# Lasermodul.net
KiCad netlist of a schematic drawn in EAGLE
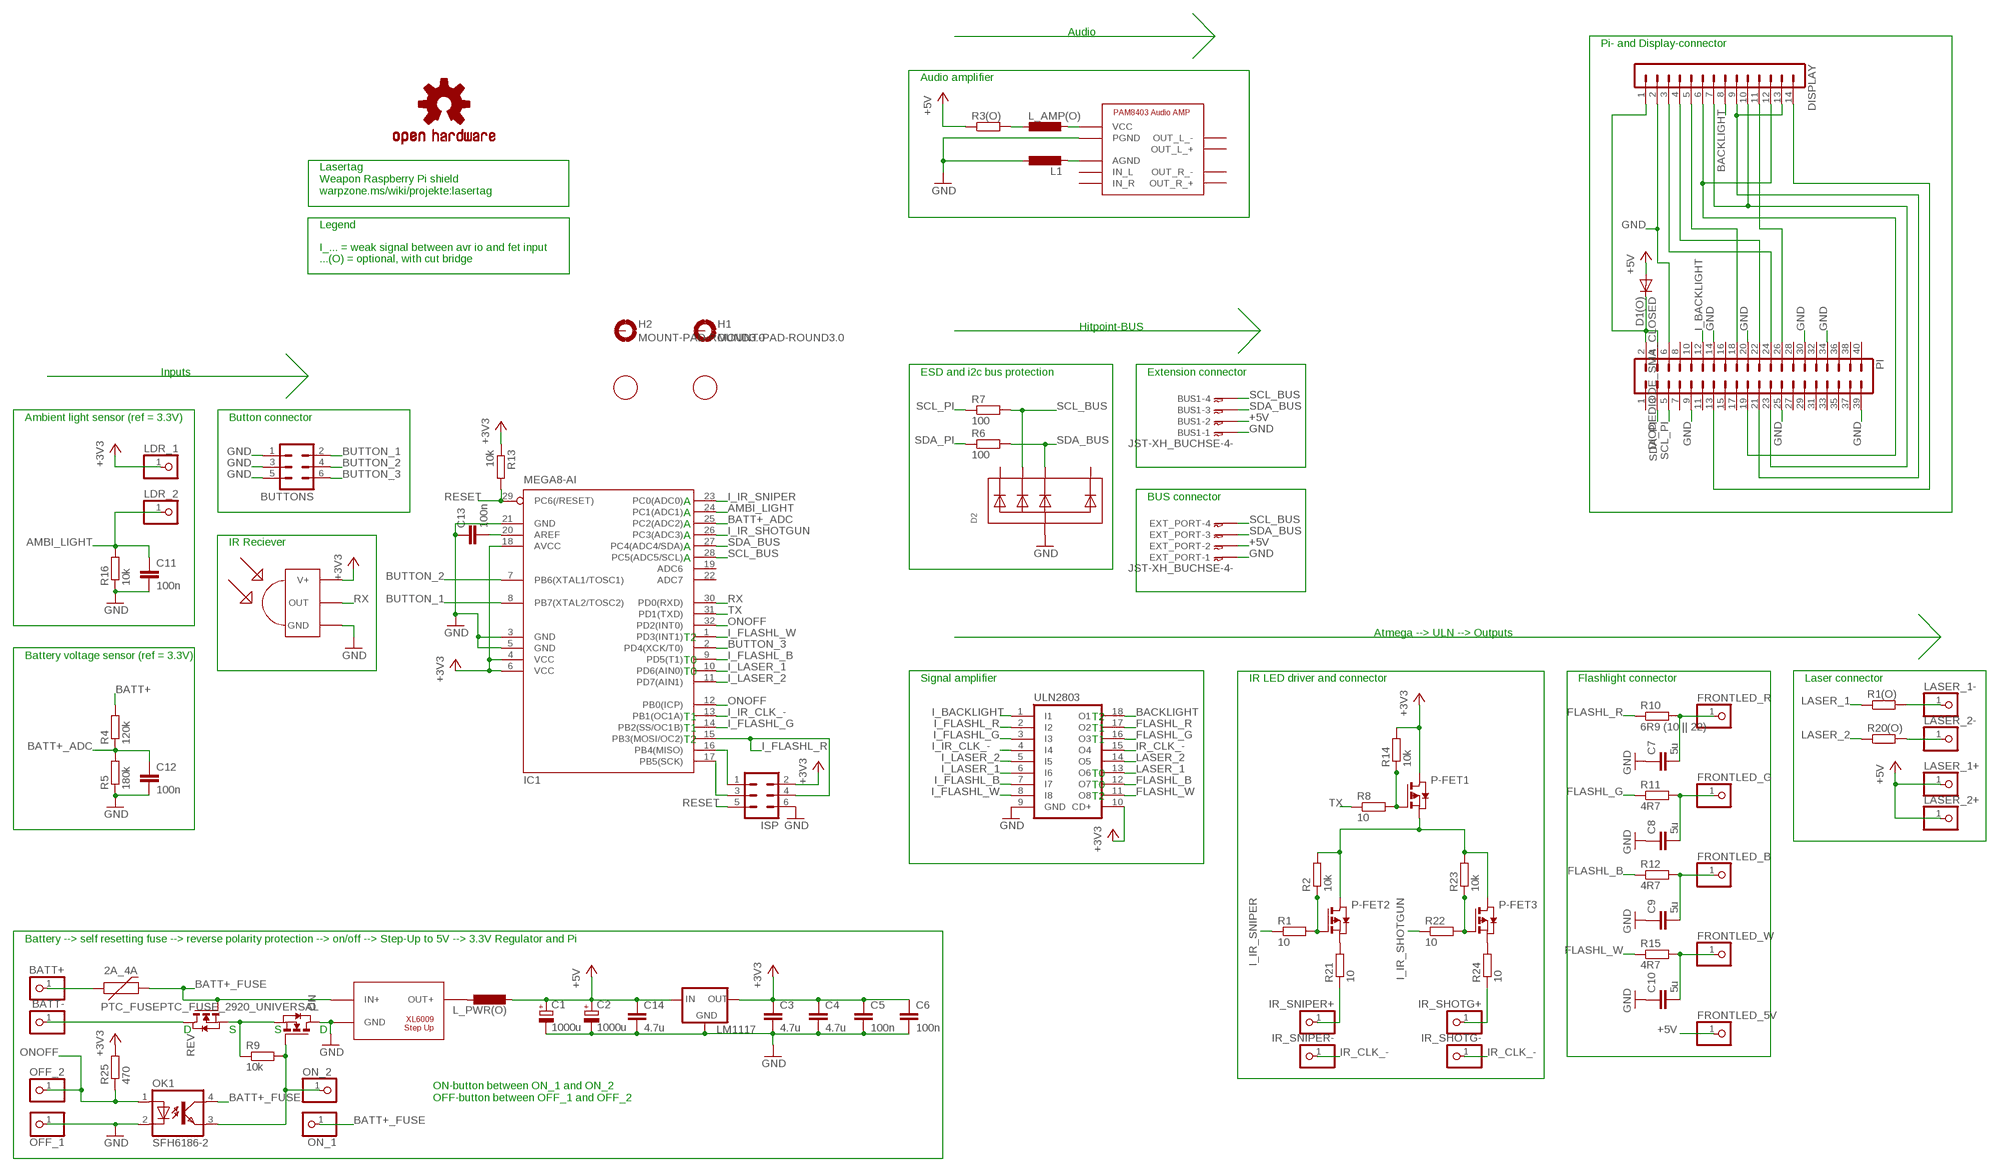
[diagram p0: schematic, sheet 1]

(export (version "E")
  (design (tool "Eeschema 10.0.6"))
  (components
    (comp (ref "2A_4A")
      (value "PTC_FUSEPTC_FUSE_2920_UNIVERSAL")
      (footprint "eagle-import:PTC_FUSE_2920_UNIVERSAL")
      (libsource (lib "eagle-import") (part "PTC_FUSEPTC_FUSE_2920_UNIVERSAL"))
    )
    (comp (ref "BATT+")
      (value "PIN-HEADER-1PIN-HEADER-1_BIG")
      (footprint "eagle-import:PIN-HEADER-1_BIG")
      (libsource (lib "eagle-import") (part "PIN-HEADER-1PIN-HEADER-1_BIG"))
    )
    (comp (ref "BATT-")
      (value "PIN-HEADER-1PIN-HEADER-1_BIG")
      (footprint "eagle-import:PIN-HEADER-1_BIG")
      (libsource (lib "eagle-import") (part "PIN-HEADER-1PIN-HEADER-1_BIG"))
    )
    (comp (ref "BUS1")
      (value "JST-XH_BUCHSE-4-")
      (footprint "eagle-import:JST-XH_BUCHSE-4")
      (libsource (lib "eagle-import") (part "JST-XH_BUCHSE-4-"))
    )
    (comp (ref "BUTTONS")
      (value "PIN-HEADER-3X2")
      (footprint "eagle-import:PIN-HEADER-3X2")
      (libsource (lib "eagle-import") (part "PIN-HEADER-3X2"))
    )
    (comp (ref "C1")
      (value "1000u")
      (footprint "eagle-import:C_UNIVERSAL_PAD")
      (libsource (lib "eagle-import") (part "C_EU_POL"))
    )
    (comp (ref "C2")
      (value "1000u")
      (footprint "eagle-import:C_UNIVERSAL_PAD")
      (libsource (lib "eagle-import") (part "C_EU_POL"))
    )
    (comp (ref "C3")
      (value "4.7u")
      (footprint "eagle-import:0805")
      (libsource (lib "eagle-import") (part "C_EU0805"))
    )
    (comp (ref "C4")
      (value "4.7u")
      (footprint "eagle-import:0805")
      (libsource (lib "eagle-import") (part "C_EU0805"))
    )
    (comp (ref "C5")
      (value "100n")
      (footprint "eagle-import:0603")
      (libsource (lib "eagle-import") (part "C_EU0603"))
    )
    (comp (ref "C6")
      (value "100n")
      (footprint "eagle-import:0603")
      (libsource (lib "eagle-import") (part "C_EU0603"))
    )
    (comp (ref "C7")
      (value "5u")
      (footprint "eagle-import:0805")
      (libsource (lib "eagle-import") (part "C_EU0805"))
    )
    (comp (ref "C8")
      (value "5u")
      (footprint "eagle-import:0805")
      (libsource (lib "eagle-import") (part "C_EU0805"))
    )
    (comp (ref "C9")
      (value "5u")
      (footprint "eagle-import:0805")
      (libsource (lib "eagle-import") (part "C_EU0805"))
    )
    (comp (ref "C10")
      (value "5u")
      (footprint "eagle-import:0805")
      (libsource (lib "eagle-import") (part "C_EU0805"))
    )
    (comp (ref "C11")
      (value "100n")
      (footprint "eagle-import:0603")
      (libsource (lib "eagle-import") (part "C_EU0603"))
    )
    (comp (ref "C12")
      (value "100n")
      (footprint "eagle-import:0603")
      (libsource (lib "eagle-import") (part "C_EU0603"))
    )
    (comp (ref "C13")
      (value "100n")
      (footprint "eagle-import:0603")
      (libsource (lib "eagle-import") (part "C_EU0603"))
    )
    (comp (ref "C14")
      (value "4.7u")
      (footprint "eagle-import:0805")
      (libsource (lib "eagle-import") (part "C_EU0805"))
    )
    (comp (ref "D1(O)")
      (value "DIODEDIODE_SMA_CLOSED")
      (footprint "eagle-import:DIODE_SMA_CLOSED")
      (libsource (lib "eagle-import") (part "DIODEDIODE_SMA_CLOSED"))
    )
    (comp (ref "D2")
      (value "ESD-SCHUTZ")
      (footprint "eagle-import:SOT363")
      (libsource (lib "eagle-import") (part "ESD-SCHUTZ"))
    )
    (comp (ref "DISPLAY")
      (value "PIN-HEADER-DISPLAY")
      (footprint "eagle-import:PIN-HEADER-DISPLAY")
      (libsource (lib "eagle-import") (part "PIN-HEADER-DISPLAY"))
    )
    (comp (ref "EXT_PORT")
      (value "JST-XH_BUCHSE-4-")
      (footprint "eagle-import:JST-XH_BUCHSE-4")
      (libsource (lib "eagle-import") (part "JST-XH_BUCHSE-4-"))
    )
    (comp (ref "FRONTLED_5V")
      (value "PIN-HEADER-1PIN-HEADER-1")
      (footprint "eagle-import:PIN-HEADER-1")
      (libsource (lib "eagle-import") (part "PIN-HEADER-1PIN-HEADER-1"))
    )
    (comp (ref "FRONTLED_B")
      (value "PIN-HEADER-1PIN-HEADER-1")
      (footprint "eagle-import:PIN-HEADER-1")
      (libsource (lib "eagle-import") (part "PIN-HEADER-1PIN-HEADER-1"))
    )
    (comp (ref "FRONTLED_G")
      (value "PIN-HEADER-1PIN-HEADER-1")
      (footprint "eagle-import:PIN-HEADER-1")
      (libsource (lib "eagle-import") (part "PIN-HEADER-1PIN-HEADER-1"))
    )
    (comp (ref "FRONTLED_R")
      (value "PIN-HEADER-1PIN-HEADER-1")
      (footprint "eagle-import:PIN-HEADER-1")
      (libsource (lib "eagle-import") (part "PIN-HEADER-1PIN-HEADER-1"))
    )
    (comp (ref "FRONTLED_W")
      (value "PIN-HEADER-1PIN-HEADER-1")
      (footprint "eagle-import:PIN-HEADER-1")
      (libsource (lib "eagle-import") (part "PIN-HEADER-1PIN-HEADER-1"))
    )
    (comp (ref "H1")
      (value "MOUNT-PAD-ROUND3.0")
      (footprint "eagle-import:3,0-PAD")
      (libsource (lib "eagle-import") (part "MOUNT-PAD-ROUND3.0"))
    )
    (comp (ref "H2")
      (value "MOUNT-PAD-ROUND3.0")
      (footprint "eagle-import:3,0-PAD")
      (libsource (lib "eagle-import") (part "MOUNT-PAD-ROUND3.0"))
    )
    (comp (ref "IC1")
      (value "MEGA8-AI")
      (footprint "eagle-import:TQFP32-08")
      (fields (field (name "MPN") "ATMEGA8-16AU"))
      (libsource (lib "eagle-import") (part "MEGA8-AI"))
    )
    (comp (ref "IR_SHOTG+")
      (value "PIN-HEADER-1PIN-HEADER-1")
      (footprint "eagle-import:PIN-HEADER-1")
      (libsource (lib "eagle-import") (part "PIN-HEADER-1PIN-HEADER-1"))
    )
    (comp (ref "IR_SHOTG-")
      (value "PIN-HEADER-1PIN-HEADER-1")
      (footprint "eagle-import:PIN-HEADER-1")
      (libsource (lib "eagle-import") (part "PIN-HEADER-1PIN-HEADER-1"))
    )
    (comp (ref "IR_SNIPER+")
      (value "PIN-HEADER-1PIN-HEADER-1")
      (footprint "eagle-import:PIN-HEADER-1")
      (libsource (lib "eagle-import") (part "PIN-HEADER-1PIN-HEADER-1"))
    )
    (comp (ref "IR_SNIPER-")
      (value "PIN-HEADER-1PIN-HEADER-1")
      (footprint "eagle-import:PIN-HEADER-1")
      (libsource (lib "eagle-import") (part "PIN-HEADER-1PIN-HEADER-1"))
    )
    (comp (ref "ISP")
      (value "PIN-HEADER-3X2")
      (footprint "eagle-import:PIN-HEADER-3X2")
      (libsource (lib "eagle-import") (part "PIN-HEADER-3X2"))
    )
    (comp (ref "L1")
      (value "L-EUL2825P")
      (footprint "eagle-import:L2825P")
      (libsource (lib "eagle-import") (part "L-EUL2825P"))
    )
    (comp (ref "LASER_1+")
      (value "PIN-HEADER-1PIN-HEADER-1")
      (footprint "eagle-import:PIN-HEADER-1")
      (libsource (lib "eagle-import") (part "PIN-HEADER-1PIN-HEADER-1"))
    )
    (comp (ref "LASER_1-")
      (value "PIN-HEADER-1PIN-HEADER-1")
      (footprint "eagle-import:PIN-HEADER-1")
      (libsource (lib "eagle-import") (part "PIN-HEADER-1PIN-HEADER-1"))
    )
    (comp (ref "LASER_2+")
      (value "PIN-HEADER-1PIN-HEADER-1")
      (footprint "eagle-import:PIN-HEADER-1")
      (libsource (lib "eagle-import") (part "PIN-HEADER-1PIN-HEADER-1"))
    )
    (comp (ref "LASER_2-")
      (value "PIN-HEADER-1PIN-HEADER-1")
      (footprint "eagle-import:PIN-HEADER-1")
      (libsource (lib "eagle-import") (part "PIN-HEADER-1PIN-HEADER-1"))
    )
    (comp (ref "LDR_1")
      (value "PIN-HEADER-1PIN-HEADER-1")
      (footprint "eagle-import:PIN-HEADER-1")
      (libsource (lib "eagle-import") (part "PIN-HEADER-1PIN-HEADER-1"))
    )
    (comp (ref "LDR_2")
      (value "PIN-HEADER-1PIN-HEADER-1")
      (footprint "eagle-import:PIN-HEADER-1")
      (libsource (lib "eagle-import") (part "PIN-HEADER-1PIN-HEADER-1"))
    )
    (comp (ref "LM1117")
      (value "LM1117_3V3_REGULATOR")
      (footprint "eagle-import:SOT223")
      (libsource (lib "eagle-import") (part "LM1117_3V3_REGULATOR"))
    )
    (comp (ref "LOGO1")
      (value "OSHW-LOGOM")
      (footprint "eagle-import:OSHW-LOGO-M")
      (libsource (lib "eagle-import") (part "OSHW-LOGOM"))
    )
    (comp (ref "L_AMP(O)")
      (value "L")
      (footprint "eagle-import:L_5MM_CLOSED")
      (libsource (lib "eagle-import") (part "L"))
    )
    (comp (ref "L_PWR(O)")
      (value "L")
      (footprint "eagle-import:L_5MM_CLOSED")
      (libsource (lib "eagle-import") (part "L"))
    )
    (comp (ref "OFF_1")
      (value "PIN-HEADER-1PIN-HEADER-1")
      (footprint "eagle-import:PIN-HEADER-1")
      (libsource (lib "eagle-import") (part "PIN-HEADER-1PIN-HEADER-1"))
    )
    (comp (ref "OFF_2")
      (value "PIN-HEADER-1PIN-HEADER-1")
      (footprint "eagle-import:PIN-HEADER-1")
      (libsource (lib "eagle-import") (part "PIN-HEADER-1PIN-HEADER-1"))
    )
    (comp (ref "OK1")
      (value "SFH6186-2")
      (footprint "eagle-import:SMD4-7")
      (fields (field (name "MF") "VISHAY/TELEFUNKEN"))
      (libsource (lib "eagle-import") (part "SFH618?6-2"))
    )
    (comp (ref "ON")
      (value "N-MOSFET")
      (footprint "eagle-import:TO252")
      (libsource (lib "eagle-import") (part "N-MOSFET"))
    )
    (comp (ref "ON_1")
      (value "PIN-HEADER-1PIN-HEADER-1")
      (footprint "eagle-import:PIN-HEADER-1")
      (libsource (lib "eagle-import") (part "PIN-HEADER-1PIN-HEADER-1"))
    )
    (comp (ref "ON_2")
      (value "PIN-HEADER-1PIN-HEADER-1")
      (footprint "eagle-import:PIN-HEADER-1")
      (libsource (lib "eagle-import") (part "PIN-HEADER-1PIN-HEADER-1"))
    )
    (comp (ref "P-FET1")
      (value "PMOSSOT23")
      (footprint "eagle-import:SOT-23")
      (libsource (lib "eagle-import") (part "PMOSSOT23"))
    )
    (comp (ref "P-FET2")
      (value "PMOSSOT23")
      (footprint "eagle-import:SOT-23")
      (libsource (lib "eagle-import") (part "PMOSSOT23"))
    )
    (comp (ref "P-FET3")
      (value "PMOSSOT23")
      (footprint "eagle-import:SOT-23")
      (libsource (lib "eagle-import") (part "PMOSSOT23"))
    )
    (comp (ref "PI")
      (value "PIN-HEADER-20X2")
      (footprint "eagle-import:PIN-HEADER-20X2")
      (libsource (lib "eagle-import") (part "PIN-HEADER-20X2"))
    )
    (comp (ref "R1")
      (value "10")
      (footprint "eagle-import:0603")
      (libsource (lib "eagle-import") (part "R_EU0603"))
    )
    (comp (ref "R1(O)")
      (value "R_EU0603_CLOSED")
      (footprint "eagle-import:0603_CLOSED")
      (libsource (lib "eagle-import") (part "R_EU0603_CLOSED"))
    )
    (comp (ref "R2")
      (value "10k")
      (footprint "eagle-import:0603")
      (libsource (lib "eagle-import") (part "R_EU0603"))
    )
    (comp (ref "R3(O)")
      (value "R_EU0805_CLOSED")
      (footprint "eagle-import:0805_CLOSED")
      (libsource (lib "eagle-import") (part "R_EU0805_CLOSED"))
    )
    (comp (ref "R4")
      (value "120k")
      (footprint "eagle-import:0603")
      (libsource (lib "eagle-import") (part "R_EU0603"))
    )
    (comp (ref "R5")
      (value "180k")
      (footprint "eagle-import:0603")
      (libsource (lib "eagle-import") (part "R_EU0603"))
    )
    (comp (ref "R6")
      (value "100")
      (footprint "eagle-import:0603")
      (libsource (lib "eagle-import") (part "R_EU0603"))
    )
    (comp (ref "R7")
      (value "100")
      (footprint "eagle-import:0603")
      (libsource (lib "eagle-import") (part "R_EU0603"))
    )
    (comp (ref "R8")
      (value "10")
      (footprint "eagle-import:0603")
      (libsource (lib "eagle-import") (part "R_EU0603"))
    )
    (comp (ref "R9")
      (value "10k")
      (footprint "eagle-import:0603")
      (libsource (lib "eagle-import") (part "R_EU0603"))
    )
    (comp (ref "R10")
      (value "6R9 (10 || 22)")
      (footprint "eagle-import:0603")
      (libsource (lib "eagle-import") (part "R_EU0603"))
    )
    (comp (ref "R11")
      (value "4R7")
      (footprint "eagle-import:0603")
      (libsource (lib "eagle-import") (part "R_EU0603"))
    )
    (comp (ref "R12")
      (value "4R7")
      (footprint "eagle-import:0603")
      (libsource (lib "eagle-import") (part "R_EU0603"))
    )
    (comp (ref "R13")
      (value "10k")
      (footprint "eagle-import:0603")
      (libsource (lib "eagle-import") (part "R_EU0603"))
    )
    (comp (ref "R14")
      (value "10k")
      (footprint "eagle-import:0603")
      (libsource (lib "eagle-import") (part "R_EU0603"))
    )
    (comp (ref "R15")
      (value "4R7")
      (footprint "eagle-import:0603")
      (libsource (lib "eagle-import") (part "R_EU0603"))
    )
    (comp (ref "R16")
      (value "10k")
      (footprint "eagle-import:0603")
      (libsource (lib "eagle-import") (part "R_EU0603"))
    )
    (comp (ref "R20(O)")
      (value "R_EU0603_CLOSED")
      (footprint "eagle-import:0603_CLOSED")
      (libsource (lib "eagle-import") (part "R_EU0603_CLOSED"))
    )
    (comp (ref "R21")
      (value "10")
      (footprint "eagle-import:0603")
      (libsource (lib "eagle-import") (part "R_EU0603"))
    )
    (comp (ref "R22")
      (value "10")
      (footprint "eagle-import:0603")
      (libsource (lib "eagle-import") (part "R_EU0603"))
    )
    (comp (ref "R23")
      (value "10k")
      (footprint "eagle-import:0603")
      (libsource (lib "eagle-import") (part "R_EU0603"))
    )
    (comp (ref "R24")
      (value "10")
      (footprint "eagle-import:0603")
      (libsource (lib "eagle-import") (part "R_EU0603"))
    )
    (comp (ref "R25")
      (value "470")
      (footprint "eagle-import:0603")
      (libsource (lib "eagle-import") (part "R_EU0603"))
    )
    (comp (ref "REV")
      (value "N-MOSFET")
      (footprint "eagle-import:TO252")
      (libsource (lib "eagle-import") (part "N-MOSFET"))
    )
    (comp (ref "U$1")
      (value "TSOP1838")
      (footprint "eagle-import:TSOP18XX")
      (libsource (lib "eagle-import") (part "TSOP1838"))
    )
    (comp (ref "U$3")
      (value "XL6009-STEPUP-BOARD")
      (footprint "eagle-import:XL6009-STEPUP-BOARD")
      (libsource (lib "eagle-import") (part "XL6009-STEPUP-BOARD"))
    )
    (comp (ref "U$4")
      (value "PAM8403-AMP-BOARD")
      (footprint "eagle-import:PAM8403-AMP-BOARD")
      (libsource (lib "eagle-import") (part "PAM8403-AMP-BOARD"))
    )
    (comp (ref "U$5")
      (value "FIDUCIAL")
      (footprint "eagle-import:FIDUCIAL_1MM")
      (libsource (lib "eagle-import") (part "FIDUCIAL"))
    )
    (comp (ref "U$6")
      (value "FIDUCIAL")
      (footprint "eagle-import:FIDUCIAL_1MM")
      (libsource (lib "eagle-import") (part "FIDUCIAL"))
    )
    (comp (ref "ULN2803")
      (value "ULN2803ASO18")
      (footprint "eagle-import:SO18W")
      (libsource (lib "eagle-import") (part "ULN2803ASO18"))
    )
  )
  (nets
    (net (code "1") (name "+3V3") (class "Default")
      (node (ref "C3") (pin "1") (pinfunction "1_1") (pintype "passive"))
      (node (ref "C4") (pin "1") (pinfunction "1_1") (pintype "passive"))
      (node (ref "C5") (pin "1") (pinfunction "1_1") (pintype "passive"))
      (node (ref "C6") (pin "1") (pinfunction "1_1") (pintype "passive"))
      (node (ref "IC1") (pin "18") (pinfunction "AVCC_18") (pintype "power_in"))
      (node (ref "IC1") (pin "4") (pinfunction "VCC_4") (pintype "power_in"))
      (node (ref "IC1") (pin "6") (pinfunction "VCC_6") (pintype "power_in"))
      (node (ref "ISP") (pin "2") (pinfunction "2_2") (pintype "passive"))
      (node (ref "LDR_1") (pin "1") (pinfunction "1_1") (pintype "passive"))
      (node (ref "LM1117") (pin "2") (pinfunction "OUT_2") (pintype "passive"))
      (node (ref "LM1117") (pin "4") (pinfunction "OUT_4") (pintype "passive"))
      (node (ref "P-FET1") (pin "1") (pinfunction "D_1") (pintype "passive"))
      (node (ref "R13") (pin "1") (pinfunction "1_1") (pintype "passive"))
      (node (ref "R14") (pin "2") (pinfunction "2_2") (pintype "passive"))
      (node (ref "R25") (pin "2") (pinfunction "2_2") (pintype "passive"))
      (node (ref "U$1") (pin "VCC") (pinfunction "V+_VCC") (pintype "bidirectional"))
      (node (ref "ULN2803") (pin "10") (pinfunction "CD+_10") (pintype "passive"))
    )
    (net (code "2") (name "+5V") (class "Default")
      (node (ref "BUS1") (pin "P$2") (pinfunction "1_P$2") (pintype "passive"))
      (node (ref "C1") (pin "+") (pinfunction "+_+") (pintype "passive"))
      (node (ref "C14") (pin "1") (pinfunction "1_1") (pintype "passive"))
      (node (ref "C2") (pin "+") (pinfunction "+_+") (pintype "passive"))
      (node (ref "D1(O)") (pin "A") (pinfunction "A_A") (pintype "passive"))
      (node (ref "EXT_PORT") (pin "P$2") (pinfunction "1_P$2") (pintype "passive"))
      (node (ref "FRONTLED_5V") (pin "1") (pinfunction "1_1") (pintype "passive"))
      (node (ref "LASER_1+") (pin "1") (pinfunction "1_1") (pintype "passive"))
      (node (ref "LASER_2+") (pin "1") (pinfunction "1_1") (pintype "passive"))
      (node (ref "LM1117") (pin "3") (pinfunction "IN_3") (pintype "input"))
      (node (ref "L_PWR(O)") (pin "2") (pinfunction "2_2") (pintype "passive"))
      (node (ref "R3(O)") (pin "1") (pinfunction "1_1") (pintype "passive"))
    )
    (net (code "3") (name "/AMBI_LIGHT") (class "Default")
      (node (ref "C11") (pin "1") (pinfunction "1_1") (pintype "passive"))
      (node (ref "IC1") (pin "24") (pinfunction "PC1(ADC1)_24") (pintype "bidirectional"))
      (node (ref "LDR_2") (pin "1") (pinfunction "1_1") (pintype "passive"))
      (node (ref "R16") (pin "2") (pinfunction "2_2") (pintype "passive"))
    )
    (net (code "4") (name "/BACKLIGHT") (class "Default")
      (node (ref "DISPLAY") (pin "8") (pinfunction "8_8") (pintype "passive"))
      (node (ref "ULN2803") (pin "18") (pinfunction "O1_18") (pintype "open_collector"))
    )
    (net (code "5") (name "/BATT+") (class "Default")
      (node (ref "2A_4A") (pin "P$1") (pinfunction "1_P$1") (pintype "bidirectional"))
      (node (ref "BATT+") (pin "1") (pinfunction "1_1") (pintype "passive"))
      (node (ref "R4") (pin "2") (pinfunction "2_2") (pintype "passive"))
    )
    (net (code "6") (name "/BATT+_ADC") (class "Default")
      (node (ref "C12") (pin "1") (pinfunction "1_1") (pintype "passive"))
      (node (ref "IC1") (pin "25") (pinfunction "PC2(ADC2)_25") (pintype "bidirectional"))
      (node (ref "R4") (pin "1") (pinfunction "1_1") (pintype "passive"))
      (node (ref "R5") (pin "2") (pinfunction "2_2") (pintype "passive"))
    )
    (net (code "7") (name "/BATT+_FUSE") (class "Default")
      (node (ref "2A_4A") (pin "P$2") (pinfunction "2_P$2") (pintype "bidirectional"))
      (node (ref "OK1") (pin "4") (pinfunction "COL_4") (pintype "passive"))
      (node (ref "ON_1") (pin "1") (pinfunction "1_1") (pintype "passive"))
      (node (ref "REV") (pin "1") (pinfunction "G_1") (pintype "passive"))
      (node (ref "U$3") (pin "IN+") (pinfunction "IN+_IN+") (pintype "passive"))
    )
    (net (code "8") (name "/BUTTON_1") (class "Default")
      (node (ref "BUTTONS") (pin "2") (pinfunction "2_2") (pintype "passive"))
      (node (ref "IC1") (pin "8") (pinfunction "PB7(XTAL2/TOSC2)_8") (pintype "bidirectional"))
    )
    (net (code "9") (name "/BUTTON_2") (class "Default")
      (node (ref "BUTTONS") (pin "4") (pinfunction "4_4") (pintype "passive"))
      (node (ref "IC1") (pin "7") (pinfunction "PB6(XTAL1/TOSC1)_7") (pintype "bidirectional"))
    )
    (net (code "10") (name "/BUTTON_3") (class "Default")
      (node (ref "BUTTONS") (pin "6") (pinfunction "6_6") (pintype "passive"))
      (node (ref "IC1") (pin "2") (pinfunction "PD4(XCK/T0)_2") (pintype "bidirectional"))
    )
    (net (code "11") (name "/FLASHL_B") (class "Default")
      (node (ref "R12") (pin "1") (pinfunction "1_1") (pintype "passive"))
      (node (ref "ULN2803") (pin "12") (pinfunction "O7_12") (pintype "open_collector"))
    )
    (net (code "12") (name "/FLASHL_G") (class "Default")
      (node (ref "R11") (pin "1") (pinfunction "1_1") (pintype "passive"))
      (node (ref "ULN2803") (pin "16") (pinfunction "O3_16") (pintype "open_collector"))
    )
    (net (code "13") (name "/FLASHL_R") (class "Default")
      (node (ref "R10") (pin "1") (pinfunction "1_1") (pintype "passive"))
      (node (ref "ULN2803") (pin "17") (pinfunction "O2_17") (pintype "open_collector"))
    )
    (net (code "14") (name "/FLASHL_W") (class "Default")
      (node (ref "R15") (pin "1") (pinfunction "1_1") (pintype "passive"))
      (node (ref "ULN2803") (pin "11") (pinfunction "O8_11") (pintype "open_collector"))
    )
    (net (code "15") (name "/IR_CLK_-") (class "Default")
      (node (ref "IR_SHOTG-") (pin "1") (pinfunction "1_1") (pintype "passive"))
      (node (ref "IR_SNIPER-") (pin "1") (pinfunction "1_1") (pintype "passive"))
      (node (ref "ULN2803") (pin "15") (pinfunction "O4_15") (pintype "open_collector"))
    )
    (net (code "16") (name "/I_BACKLIGHT") (class "Default")
      (node (ref "PI") (pin "12") (pinfunction "12_12") (pintype "passive"))
      (node (ref "ULN2803") (pin "1") (pinfunction "I1_1") (pintype "input"))
    )
    (net (code "17") (name "/I_FLASHL_B") (class "Default")
      (node (ref "IC1") (pin "9") (pinfunction "PD5(T1)_9") (pintype "bidirectional"))
      (node (ref "ULN2803") (pin "7") (pinfunction "I7_7") (pintype "input"))
    )
    (net (code "18") (name "/I_FLASHL_G") (class "Default")
      (node (ref "IC1") (pin "14") (pinfunction "PB2(SS/OC1B)_14") (pintype "bidirectional"))
      (node (ref "ULN2803") (pin "3") (pinfunction "I3_3") (pintype "input"))
    )
    (net (code "19") (name "/I_FLASHL_R") (class "Default")
      (node (ref "IC1") (pin "15") (pinfunction "PB3(MOSI/OC2)_15") (pintype "bidirectional"))
      (node (ref "ISP") (pin "4") (pinfunction "4_4") (pintype "passive"))
      (node (ref "ULN2803") (pin "2") (pinfunction "I2_2") (pintype "input"))
    )
    (net (code "20") (name "/I_FLASHL_W") (class "Default")
      (node (ref "IC1") (pin "1") (pinfunction "PD3(INT1)_1") (pintype "bidirectional"))
      (node (ref "ULN2803") (pin "8") (pinfunction "I8_8") (pintype "input"))
    )
    (net (code "21") (name "/I_IR_CLK_-") (class "Default")
      (node (ref "IC1") (pin "13") (pinfunction "PB1(OC1A)_13") (pintype "bidirectional"))
      (node (ref "ULN2803") (pin "4") (pinfunction "I4_4") (pintype "input"))
    )
    (net (code "22") (name "/I_IR_SHOTGUN") (class "Default")
      (node (ref "IC1") (pin "26") (pinfunction "PC3(ADC3)_26") (pintype "bidirectional"))
      (node (ref "R22") (pin "1") (pinfunction "1_1") (pintype "passive"))
    )
    (net (code "23") (name "/I_IR_SNIPER") (class "Default")
      (node (ref "IC1") (pin "23") (pinfunction "PC0(ADC0)_23") (pintype "bidirectional"))
      (node (ref "R1") (pin "1") (pinfunction "1_1") (pintype "passive"))
    )
    (net (code "24") (name "/I_LASER_1") (class "Default")
      (node (ref "IC1") (pin "10") (pinfunction "PD6(AIN0)_10") (pintype "bidirectional"))
      (node (ref "ULN2803") (pin "6") (pinfunction "I6_6") (pintype "input"))
    )
    (net (code "25") (name "/I_LASER_2") (class "Default")
      (node (ref "IC1") (pin "11") (pinfunction "PD7(AIN1)_11") (pintype "bidirectional"))
      (node (ref "ULN2803") (pin "5") (pinfunction "I5_5") (pintype "input"))
    )
    (net (code "26") (name "/LASER_1") (class "Default")
      (node (ref "R1(O)") (pin "1") (pinfunction "1_1") (pintype "passive"))
      (node (ref "ULN2803") (pin "13") (pinfunction "O6_13") (pintype "open_collector"))
    )
    (net (code "27") (name "/LASER_2") (class "Default")
      (node (ref "R20(O)") (pin "1") (pinfunction "1_1") (pintype "passive"))
      (node (ref "ULN2803") (pin "14") (pinfunction "O5_14") (pintype "open_collector"))
    )
    (net (code "28") (name "/ONOFF") (class "Default")
      (node (ref "IC1") (pin "12") (pinfunction "PB0(ICP)_12") (pintype "bidirectional"))
      (node (ref "IC1") (pin "32") (pinfunction "PD2(INT0)_32") (pintype "bidirectional"))
      (node (ref "OFF_2") (pin "1") (pinfunction "1_1") (pintype "passive"))
      (node (ref "OK1") (pin "1") (pinfunction "A_1") (pintype "passive"))
      (node (ref "R25") (pin "1") (pinfunction "1_1") (pintype "passive"))
    )
    (net (code "29") (name "/RESET") (class "Default")
      (node (ref "IC1") (pin "29") (pinfunction "PC6(/RESET)_29") (pintype "bidirectional"))
      (node (ref "ISP") (pin "5") (pinfunction "5_5") (pintype "passive"))
      (node (ref "R13") (pin "2") (pinfunction "2_2") (pintype "passive"))
    )
    (net (code "30") (name "/RX") (class "Default")
      (node (ref "IC1") (pin "30") (pinfunction "PD0(RXD)_30") (pintype "bidirectional"))
      (node (ref "U$1") (pin "OUT") (pinfunction "OUT_OUT") (pintype "bidirectional"))
    )
    (net (code "31") (name "/SCL_BUS") (class "Default")
      (node (ref "BUS1") (pin "P$4") (pinfunction "1_P$4") (pintype "passive"))
      (node (ref "D2") (pin "3") (pinfunction "C2_3") (pintype "passive"))
      (node (ref "EXT_PORT") (pin "P$4") (pinfunction "1_P$4") (pintype "passive"))
      (node (ref "IC1") (pin "28") (pinfunction "PC5(ADC5/SCL)_28") (pintype "bidirectional"))
      (node (ref "R7") (pin "2") (pinfunction "2_2") (pintype "passive"))
    )
    (net (code "32") (name "/SCL_PI") (class "Default")
      (node (ref "PI") (pin "5") (pinfunction "5_5") (pintype "passive"))
      (node (ref "R7") (pin "1") (pinfunction "1_1") (pintype "passive"))
    )
    (net (code "33") (name "/SDA_BUS") (class "Default")
      (node (ref "BUS1") (pin "P$3") (pinfunction "1_P$3") (pintype "passive"))
      (node (ref "D2") (pin "4") (pinfunction "C3_4") (pintype "passive"))
      (node (ref "EXT_PORT") (pin "P$3") (pinfunction "1_P$3") (pintype "passive"))
      (node (ref "IC1") (pin "27") (pinfunction "PC4(ADC4/SDA)_27") (pintype "bidirectional"))
      (node (ref "R6") (pin "2") (pinfunction "2_2") (pintype "passive"))
    )
    (net (code "34") (name "/SDA_PI") (class "Default")
      (node (ref "PI") (pin "3") (pinfunction "3_3") (pintype "passive"))
      (node (ref "R6") (pin "1") (pinfunction "1_1") (pintype "passive"))
    )
    (net (code "35") (name "/TX") (class "Default")
      (node (ref "IC1") (pin "31") (pinfunction "PD1(TXD)_31") (pintype "bidirectional"))
      (node (ref "R8") (pin "1") (pinfunction "1_1") (pintype "passive"))
    )
    (net (code "36") (name "GND") (class "Default")
      (node (ref "BUS1") (pin "P$1") (pinfunction "1_P$1") (pintype "passive"))
      (node (ref "BUTTONS") (pin "1") (pinfunction "1_1") (pintype "passive"))
      (node (ref "BUTTONS") (pin "3") (pinfunction "3_3") (pintype "passive"))
      (node (ref "BUTTONS") (pin "5") (pinfunction "5_5") (pintype "passive"))
      (node (ref "C1") (pin "-") (pinfunction "-_-") (pintype "passive"))
      (node (ref "C10") (pin "1") (pinfunction "1_1") (pintype "passive"))
      (node (ref "C11") (pin "2") (pinfunction "2_2") (pintype "passive"))
      (node (ref "C12") (pin "2") (pinfunction "2_2") (pintype "passive"))
      (node (ref "C13") (pin "1") (pinfunction "1_1") (pintype "passive"))
      (node (ref "C14") (pin "2") (pinfunction "2_2") (pintype "passive"))
      (node (ref "C2") (pin "-") (pinfunction "-_-") (pintype "passive"))
      (node (ref "C3") (pin "2") (pinfunction "2_2") (pintype "passive"))
      (node (ref "C4") (pin "2") (pinfunction "2_2") (pintype "passive"))
      (node (ref "C5") (pin "2") (pinfunction "2_2") (pintype "passive"))
      (node (ref "C6") (pin "2") (pinfunction "2_2") (pintype "passive"))
      (node (ref "C7") (pin "1") (pinfunction "1_1") (pintype "passive"))
      (node (ref "C8") (pin "1") (pinfunction "1_1") (pintype "passive"))
      (node (ref "C9") (pin "1") (pinfunction "1_1") (pintype "passive"))
      (node (ref "D2") (pin "2") (pinfunction "A_2") (pintype "passive"))
      (node (ref "DISPLAY") (pin "2") (pinfunction "2_2") (pintype "passive"))
      (node (ref "EXT_PORT") (pin "P$1") (pinfunction "1_P$1") (pintype "passive"))
      (node (ref "IC1") (pin "21") (pinfunction "GND_21") (pintype "power_in"))
      (node (ref "IC1") (pin "3") (pinfunction "GND_3") (pintype "power_in"))
      (node (ref "IC1") (pin "5") (pinfunction "GND_5") (pintype "power_in"))
      (node (ref "ISP") (pin "6") (pinfunction "6_6") (pintype "passive"))
      (node (ref "L1") (pin "1") (pinfunction "1_1") (pintype "passive"))
      (node (ref "LM1117") (pin "1") (pinfunction "GND_1") (pintype "input"))
      (node (ref "OFF_1") (pin "1") (pinfunction "1_1") (pintype "passive"))
      (node (ref "OK1") (pin "2") (pinfunction "C_2") (pintype "passive"))
      (node (ref "ON") (pin "3") (pinfunction "D_3") (pintype "passive"))
      (node (ref "PI") (pin "14") (pinfunction "14_14") (pintype "passive"))
      (node (ref "PI") (pin "20") (pinfunction "20_20") (pintype "passive"))
      (node (ref "PI") (pin "25") (pinfunction "25_25") (pintype "passive"))
      (node (ref "PI") (pin "30") (pinfunction "30_30") (pintype "passive"))
      (node (ref "PI") (pin "34") (pinfunction "34_34") (pintype "passive"))
      (node (ref "PI") (pin "39") (pinfunction "39_39") (pintype "passive"))
      (node (ref "PI") (pin "6") (pinfunction "6_6") (pintype "passive"))
      (node (ref "PI") (pin "9") (pinfunction "9_9") (pintype "passive"))
      (node (ref "R16") (pin "1") (pinfunction "1_1") (pintype "passive"))
      (node (ref "R5") (pin "1") (pinfunction "1_1") (pintype "passive"))
      (node (ref "U$1") (pin "GND") (pinfunction "GND_GND") (pintype "bidirectional"))
      (node (ref "U$3") (pin "GND_IN") (pinfunction "GND_GND_IN") (pintype "power_in"))
      (node (ref "U$3") (pin "GND_OUT") (pinfunction "GND_GND_OUT") (pintype "power_in"))
      (node (ref "U$4") (pin "PGND") (pinfunction "PGND_PGND") (pintype "power_in"))
      (node (ref "ULN2803") (pin "9") (pinfunction "GND_9") (pintype "power_in"))
    )
    (net (code "37") (name "Net-(C7-Pad2)") (class "Default")
      (node (ref "C7") (pin "2") (pinfunction "2_2") (pintype "passive"))
      (node (ref "FRONTLED_R") (pin "1") (pinfunction "1_1") (pintype "passive"))
      (node (ref "R10") (pin "2") (pinfunction "2_2") (pintype "passive"))
    )
    (net (code "38") (name "Net-(C8-Pad2)") (class "Default")
      (node (ref "C8") (pin "2") (pinfunction "2_2") (pintype "passive"))
      (node (ref "FRONTLED_G") (pin "1") (pinfunction "1_1") (pintype "passive"))
      (node (ref "R11") (pin "2") (pinfunction "2_2") (pintype "passive"))
    )
    (net (code "39") (name "Net-(C9-Pad2)") (class "Default")
      (node (ref "C9") (pin "2") (pinfunction "2_2") (pintype "passive"))
      (node (ref "FRONTLED_B") (pin "1") (pinfunction "1_1") (pintype "passive"))
      (node (ref "R12") (pin "2") (pinfunction "2_2") (pintype "passive"))
    )
    (net (code "40") (name "Net-(C10-Pad2)") (class "Default")
      (node (ref "C10") (pin "2") (pinfunction "2_2") (pintype "passive"))
      (node (ref "FRONTLED_W") (pin "1") (pinfunction "1_1") (pintype "passive"))
      (node (ref "R15") (pin "2") (pinfunction "2_2") (pintype "passive"))
    )
    (net (code "41") (name "Net-(D1(O)-PadC)") (class "Default")
      (node (ref "D1(O)") (pin "C") (pinfunction "C_C") (pintype "passive"))
      (node (ref "DISPLAY") (pin "1") (pinfunction "1_1") (pintype "passive"))
      (node (ref "PI") (pin "2") (pinfunction "2_2") (pintype "passive"))
      (node (ref "PI") (pin "4") (pinfunction "4_4") (pintype "passive"))
    )
    (net (code "42") (name "Net-(DISPLAY-Pad3)") (class "Default")
      (node (ref "DISPLAY") (pin "3") (pinfunction "3_3") (pintype "passive"))
      (node (ref "PI") (pin "24") (pinfunction "24_24") (pintype "passive"))
    )
    (net (code "43") (name "Net-(DISPLAY-Pad4)") (class "Default")
      (node (ref "DISPLAY") (pin "4") (pinfunction "4_4") (pintype "passive"))
      (node (ref "PI") (pin "22") (pinfunction "22_22") (pintype "passive"))
    )
    (net (code "44") (name "Net-(DISPLAY-Pad5)") (class "Default")
      (node (ref "DISPLAY") (pin "5") (pinfunction "5_5") (pintype "passive"))
      (node (ref "PI") (pin "18") (pinfunction "18_18") (pintype "passive"))
    )
    (net (code "45") (name "Net-(DISPLAY-Pad10)") (class "Default")
      (node (ref "DISPLAY") (pin "10") (pinfunction "10_10") (pintype "passive"))
      (node (ref "DISPLAY") (pin "7") (pinfunction "7_7") (pintype "passive"))
      (node (ref "PI") (pin "23") (pinfunction "23_23") (pintype "passive"))
    )
    (net (code "46") (name "Net-(DISPLAY-Pad11)") (class "Default")
      (node (ref "DISPLAY") (pin "11") (pinfunction "11_11") (pintype "passive"))
      (node (ref "PI") (pin "26") (pinfunction "26_26") (pintype "passive"))
    )
    (net (code "47") (name "Net-(DISPLAY-Pad12)") (class "Default")
      (node (ref "DISPLAY") (pin "12") (pinfunction "12_12") (pintype "passive"))
      (node (ref "DISPLAY") (pin "6") (pinfunction "6_6") (pintype "passive"))
      (node (ref "PI") (pin "19") (pinfunction "19_19") (pintype "passive"))
    )
    (net (code "48") (name "Net-(DISPLAY-Pad13)") (class "Default")
      (node (ref "DISPLAY") (pin "13") (pinfunction "13_13") (pintype "passive"))
      (node (ref "DISPLAY") (pin "9") (pinfunction "9_9") (pintype "passive"))
      (node (ref "PI") (pin "21") (pinfunction "21_21") (pintype "passive"))
    )
    (net (code "49") (name "Net-(DISPLAY-Pad14)") (class "Default")
      (node (ref "DISPLAY") (pin "14") (pinfunction "14_14") (pintype "passive"))
      (node (ref "PI") (pin "13") (pinfunction "13_13") (pintype "passive"))
    )
    (net (code "50") (name "Net-(IC1-AREF)") (class "Default")
      (node (ref "C13") (pin "2") (pinfunction "2_2") (pintype "passive"))
      (node (ref "IC1") (pin "20") (pinfunction "AREF_20") (pintype "passive"))
    )
    (net (code "51") (name "Net-(IC1-PB4(MISO))") (class "Default")
      (node (ref "IC1") (pin "16") (pinfunction "PB4(MISO)_16") (pintype "bidirectional"))
      (node (ref "ISP") (pin "1") (pinfunction "1_1") (pintype "passive"))
    )
    (net (code "52") (name "Net-(IC1-PB5(SCK))") (class "Default")
      (node (ref "IC1") (pin "17") (pinfunction "PB5(SCK)_17") (pintype "bidirectional"))
      (node (ref "ISP") (pin "3") (pinfunction "3_3") (pintype "passive"))
    )
    (net (code "53") (name "Net-(IR_SHOTG+-Pad1)") (class "Default")
      (node (ref "IR_SHOTG+") (pin "1") (pinfunction "1_1") (pintype "passive"))
      (node (ref "R24") (pin "1") (pinfunction "1_1") (pintype "passive"))
    )
    (net (code "54") (name "Net-(IR_SNIPER+-Pad1)") (class "Default")
      (node (ref "IR_SNIPER+") (pin "1") (pinfunction "1_1") (pintype "passive"))
      (node (ref "R21") (pin "1") (pinfunction "1_1") (pintype "passive"))
    )
    (net (code "55") (name "Net-(L1-Pad2)") (class "Default")
      (node (ref "L1") (pin "2") (pinfunction "2_2") (pintype "passive"))
      (node (ref "U$4") (pin "AGND") (pinfunction "AGND_AGND") (pintype "passive"))
    )
    (net (code "56") (name "Net-(LASER_1--Pad1)") (class "Default")
      (node (ref "LASER_1-") (pin "1") (pinfunction "1_1") (pintype "passive"))
      (node (ref "R1(O)") (pin "2") (pinfunction "2_2") (pintype "passive"))
    )
    (net (code "57") (name "Net-(LASER_2--Pad1)") (class "Default")
      (node (ref "LASER_2-") (pin "1") (pinfunction "1_1") (pintype "passive"))
      (node (ref "R20(O)") (pin "2") (pinfunction "2_2") (pintype "passive"))
    )
    (net (code "58") (name "Net-(L_AMP(O)-Pad1)") (class "Default")
      (node (ref "L_AMP(O)") (pin "1") (pinfunction "1_1") (pintype "passive"))
      (node (ref "U$4") (pin "VCC") (pinfunction "VCC_VCC") (pintype "power_in"))
    )
    (net (code "59") (name "Net-(L_AMP(O)-Pad2)") (class "Default")
      (node (ref "L_AMP(O)") (pin "2") (pinfunction "2_2") (pintype "passive"))
      (node (ref "R3(O)") (pin "2") (pinfunction "2_2") (pintype "passive"))
    )
    (net (code "60") (name "Net-(L_PWR(O)-Pad1)") (class "Default")
      (node (ref "L_PWR(O)") (pin "1") (pinfunction "1_1") (pintype "passive"))
      (node (ref "U$3") (pin "OUT+") (pinfunction "OUT+_OUT+") (pintype "power_in"))
    )
    (net (code "61") (name "Net-(OK1-EMIT)") (class "Default")
      (node (ref "OK1") (pin "3") (pinfunction "EMIT_3") (pintype "passive"))
      (node (ref "ON") (pin "1") (pinfunction "G_1") (pintype "passive"))
      (node (ref "ON_2") (pin "1") (pinfunction "1_1") (pintype "passive"))
      (node (ref "R9") (pin "2") (pinfunction "2_2") (pintype "passive"))
    )
    (net (code "62") (name "Net-(ON-S)") (class "Default")
      (node (ref "ON") (pin "2") (pinfunction "S_2") (pintype "passive"))
      (node (ref "R9") (pin "1") (pinfunction "1_1") (pintype "passive"))
      (node (ref "REV") (pin "2") (pinfunction "S_2") (pintype "passive"))
    )
    (net (code "63") (name "Net-(P-FET1-G)") (class "Default")
      (node (ref "P-FET1") (pin "3") (pinfunction "G_3") (pintype "passive"))
      (node (ref "R14") (pin "1") (pinfunction "1_1") (pintype "passive"))
      (node (ref "R8") (pin "2") (pinfunction "2_2") (pintype "passive"))
    )
    (net (code "64") (name "Net-(P-FET1-S)") (class "Default")
      (node (ref "P-FET1") (pin "2") (pinfunction "S_2") (pintype "passive"))
      (node (ref "P-FET2") (pin "1") (pinfunction "D_1") (pintype "passive"))
      (node (ref "P-FET3") (pin "1") (pinfunction "D_1") (pintype "passive"))
      (node (ref "R2") (pin "2") (pinfunction "2_2") (pintype "passive"))
      (node (ref "R23") (pin "2") (pinfunction "2_2") (pintype "passive"))
    )
    (net (code "65") (name "Net-(P-FET2-G)") (class "Default")
      (node (ref "P-FET2") (pin "3") (pinfunction "G_3") (pintype "passive"))
      (node (ref "R1") (pin "2") (pinfunction "2_2") (pintype "passive"))
      (node (ref "R2") (pin "1") (pinfunction "1_1") (pintype "passive"))
    )
    (net (code "66") (name "Net-(P-FET2-S)") (class "Default")
      (node (ref "P-FET2") (pin "2") (pinfunction "S_2") (pintype "passive"))
      (node (ref "R21") (pin "2") (pinfunction "2_2") (pintype "passive"))
    )
    (net (code "67") (name "Net-(P-FET3-G)") (class "Default")
      (node (ref "P-FET3") (pin "3") (pinfunction "G_3") (pintype "passive"))
      (node (ref "R22") (pin "2") (pinfunction "2_2") (pintype "passive"))
      (node (ref "R23") (pin "1") (pinfunction "1_1") (pintype "passive"))
    )
    (net (code "68") (name "Net-(P-FET3-S)") (class "Default")
      (node (ref "P-FET3") (pin "2") (pinfunction "S_2") (pintype "passive"))
      (node (ref "R24") (pin "2") (pinfunction "2_2") (pintype "passive"))
    )
    (net (code "69") (name "Net-(REV-D)") (class "Default")
      (node (ref "BATT-") (pin "1") (pinfunction "1_1") (pintype "passive"))
      (node (ref "REV") (pin "3") (pinfunction "D_3") (pintype "passive"))
    )
    (net (code "70") (name "unconnected-(D2-C1-Pad1)") (class "Default")
      (node (ref "D2") (pin "1") (pinfunction "C1_1") (pintype "passive"))
    )
    (net (code "71") (name "unconnected-(D2-C5-Pad6)") (class "Default")
      (node (ref "D2") (pin "6") (pinfunction "C5_6") (pintype "passive"))
    )
    (net (code "72") (name "unconnected-(H1-MOUNT-PadB3,0)") (class "Default")
      (node (ref "H1") (pin "B3,0") (pinfunction "MOUNT_B3,0") (pintype "passive"))
    )
    (net (code "73") (name "unconnected-(H2-MOUNT-PadB3,0)") (class "Default")
      (node (ref "H2") (pin "B3,0") (pinfunction "MOUNT_B3,0") (pintype "passive"))
    )
    (net (code "74") (name "unconnected-(IC1-ADC6-Pad19)") (class "Default")
      (node (ref "IC1") (pin "19") (pinfunction "ADC6_19") (pintype "bidirectional"))
    )
    (net (code "75") (name "unconnected-(IC1-ADC7-Pad22)") (class "Default")
      (node (ref "IC1") (pin "22") (pinfunction "ADC7_22") (pintype "bidirectional"))
    )
    (net (code "76") (name "unconnected-(PI-Pad1)") (class "Default")
      (node (ref "PI") (pin "1") (pinfunction "1_1") (pintype "passive"))
    )
    (net (code "77") (name "unconnected-(PI-Pad7)") (class "Default")
      (node (ref "PI") (pin "7") (pinfunction "7_7") (pintype "passive"))
    )
    (net (code "78") (name "unconnected-(PI-Pad8)") (class "Default")
      (node (ref "PI") (pin "8") (pinfunction "8_8") (pintype "passive"))
    )
    (net (code "79") (name "unconnected-(PI-Pad10)") (class "Default")
      (node (ref "PI") (pin "10") (pinfunction "10_10") (pintype "passive"))
    )
    (net (code "80") (name "unconnected-(PI-Pad11)") (class "Default")
      (node (ref "PI") (pin "11") (pinfunction "11_11") (pintype "passive"))
    )
    (net (code "81") (name "unconnected-(PI-Pad15)") (class "Default")
      (node (ref "PI") (pin "15") (pinfunction "15_15") (pintype "passive"))
    )
    (net (code "82") (name "unconnected-(PI-Pad16)") (class "Default")
      (node (ref "PI") (pin "16") (pinfunction "16_16") (pintype "passive"))
    )
    (net (code "83") (name "unconnected-(PI-Pad17)") (class "Default")
      (node (ref "PI") (pin "17") (pinfunction "17_17") (pintype "passive"))
    )
    (net (code "84") (name "unconnected-(PI-Pad27)") (class "Default")
      (node (ref "PI") (pin "27") (pinfunction "27_27") (pintype "passive"))
    )
    (net (code "85") (name "unconnected-(PI-Pad28)") (class "Default")
      (node (ref "PI") (pin "28") (pinfunction "28_28") (pintype "passive"))
    )
    (net (code "86") (name "unconnected-(PI-Pad29)") (class "Default")
      (node (ref "PI") (pin "29") (pinfunction "29_29") (pintype "passive"))
    )
    (net (code "87") (name "unconnected-(PI-Pad31)") (class "Default")
      (node (ref "PI") (pin "31") (pinfunction "31_31") (pintype "passive"))
    )
    (net (code "88") (name "unconnected-(PI-Pad32)") (class "Default")
      (node (ref "PI") (pin "32") (pinfunction "32_32") (pintype "passive"))
    )
    (net (code "89") (name "unconnected-(PI-Pad33)") (class "Default")
      (node (ref "PI") (pin "33") (pinfunction "33_33") (pintype "passive"))
    )
    (net (code "90") (name "unconnected-(PI-Pad35)") (class "Default")
      (node (ref "PI") (pin "35") (pinfunction "35_35") (pintype "passive"))
    )
    (net (code "91") (name "unconnected-(PI-Pad36)") (class "Default")
      (node (ref "PI") (pin "36") (pinfunction "36_36") (pintype "passive"))
    )
    (net (code "92") (name "unconnected-(PI-Pad37)") (class "Default")
      (node (ref "PI") (pin "37") (pinfunction "37_37") (pintype "passive"))
    )
    (net (code "93") (name "unconnected-(PI-Pad38)") (class "Default")
      (node (ref "PI") (pin "38") (pinfunction "38_38") (pintype "passive"))
    )
    (net (code "94") (name "unconnected-(PI-Pad40)") (class "Default")
      (node (ref "PI") (pin "40") (pinfunction "40_40") (pintype "passive"))
    )
    (net (code "95") (name "unconnected-(U$4-PadIN_L)") (class "Default")
      (node (ref "U$4") (pin "IN_L") (pinfunction "IN_L_IN_L") (pintype "input"))
    )
    (net (code "96") (name "unconnected-(U$4-PadIN_R)") (class "Default")
      (node (ref "U$4") (pin "IN_R") (pinfunction "IN_R_IN_R") (pintype "input"))
    )
    (net (code "97") (name "unconnected-(U$4-PadOUT_L_+)") (class "Default")
      (node (ref "U$4") (pin "OUT_L_+") (pinfunction "OUT_L_+_OUT_L_+") (pintype "output"))
    )
    (net (code "98") (name "unconnected-(U$4-PadOUT_L_-)") (class "Default")
      (node (ref "U$4") (pin "OUT_L_-") (pinfunction "OUT_L_-_OUT_L_-") (pintype "output"))
    )
    (net (code "99") (name "unconnected-(U$4-PadOUT_R_+)") (class "Default")
      (node (ref "U$4") (pin "OUT_R_+") (pinfunction "OUT_R_+_OUT_R_+") (pintype "output"))
    )
    (net (code "100") (name "unconnected-(U$4-PadOUT_R_-)") (class "Default")
      (node (ref "U$4") (pin "OUT_R_-") (pinfunction "OUT_R_-_OUT_R_-") (pintype "output"))
    )
  )
)
